# Power_Sources_and_Supply.net
KiCad netlist of a schematic drawn in Altium Designer
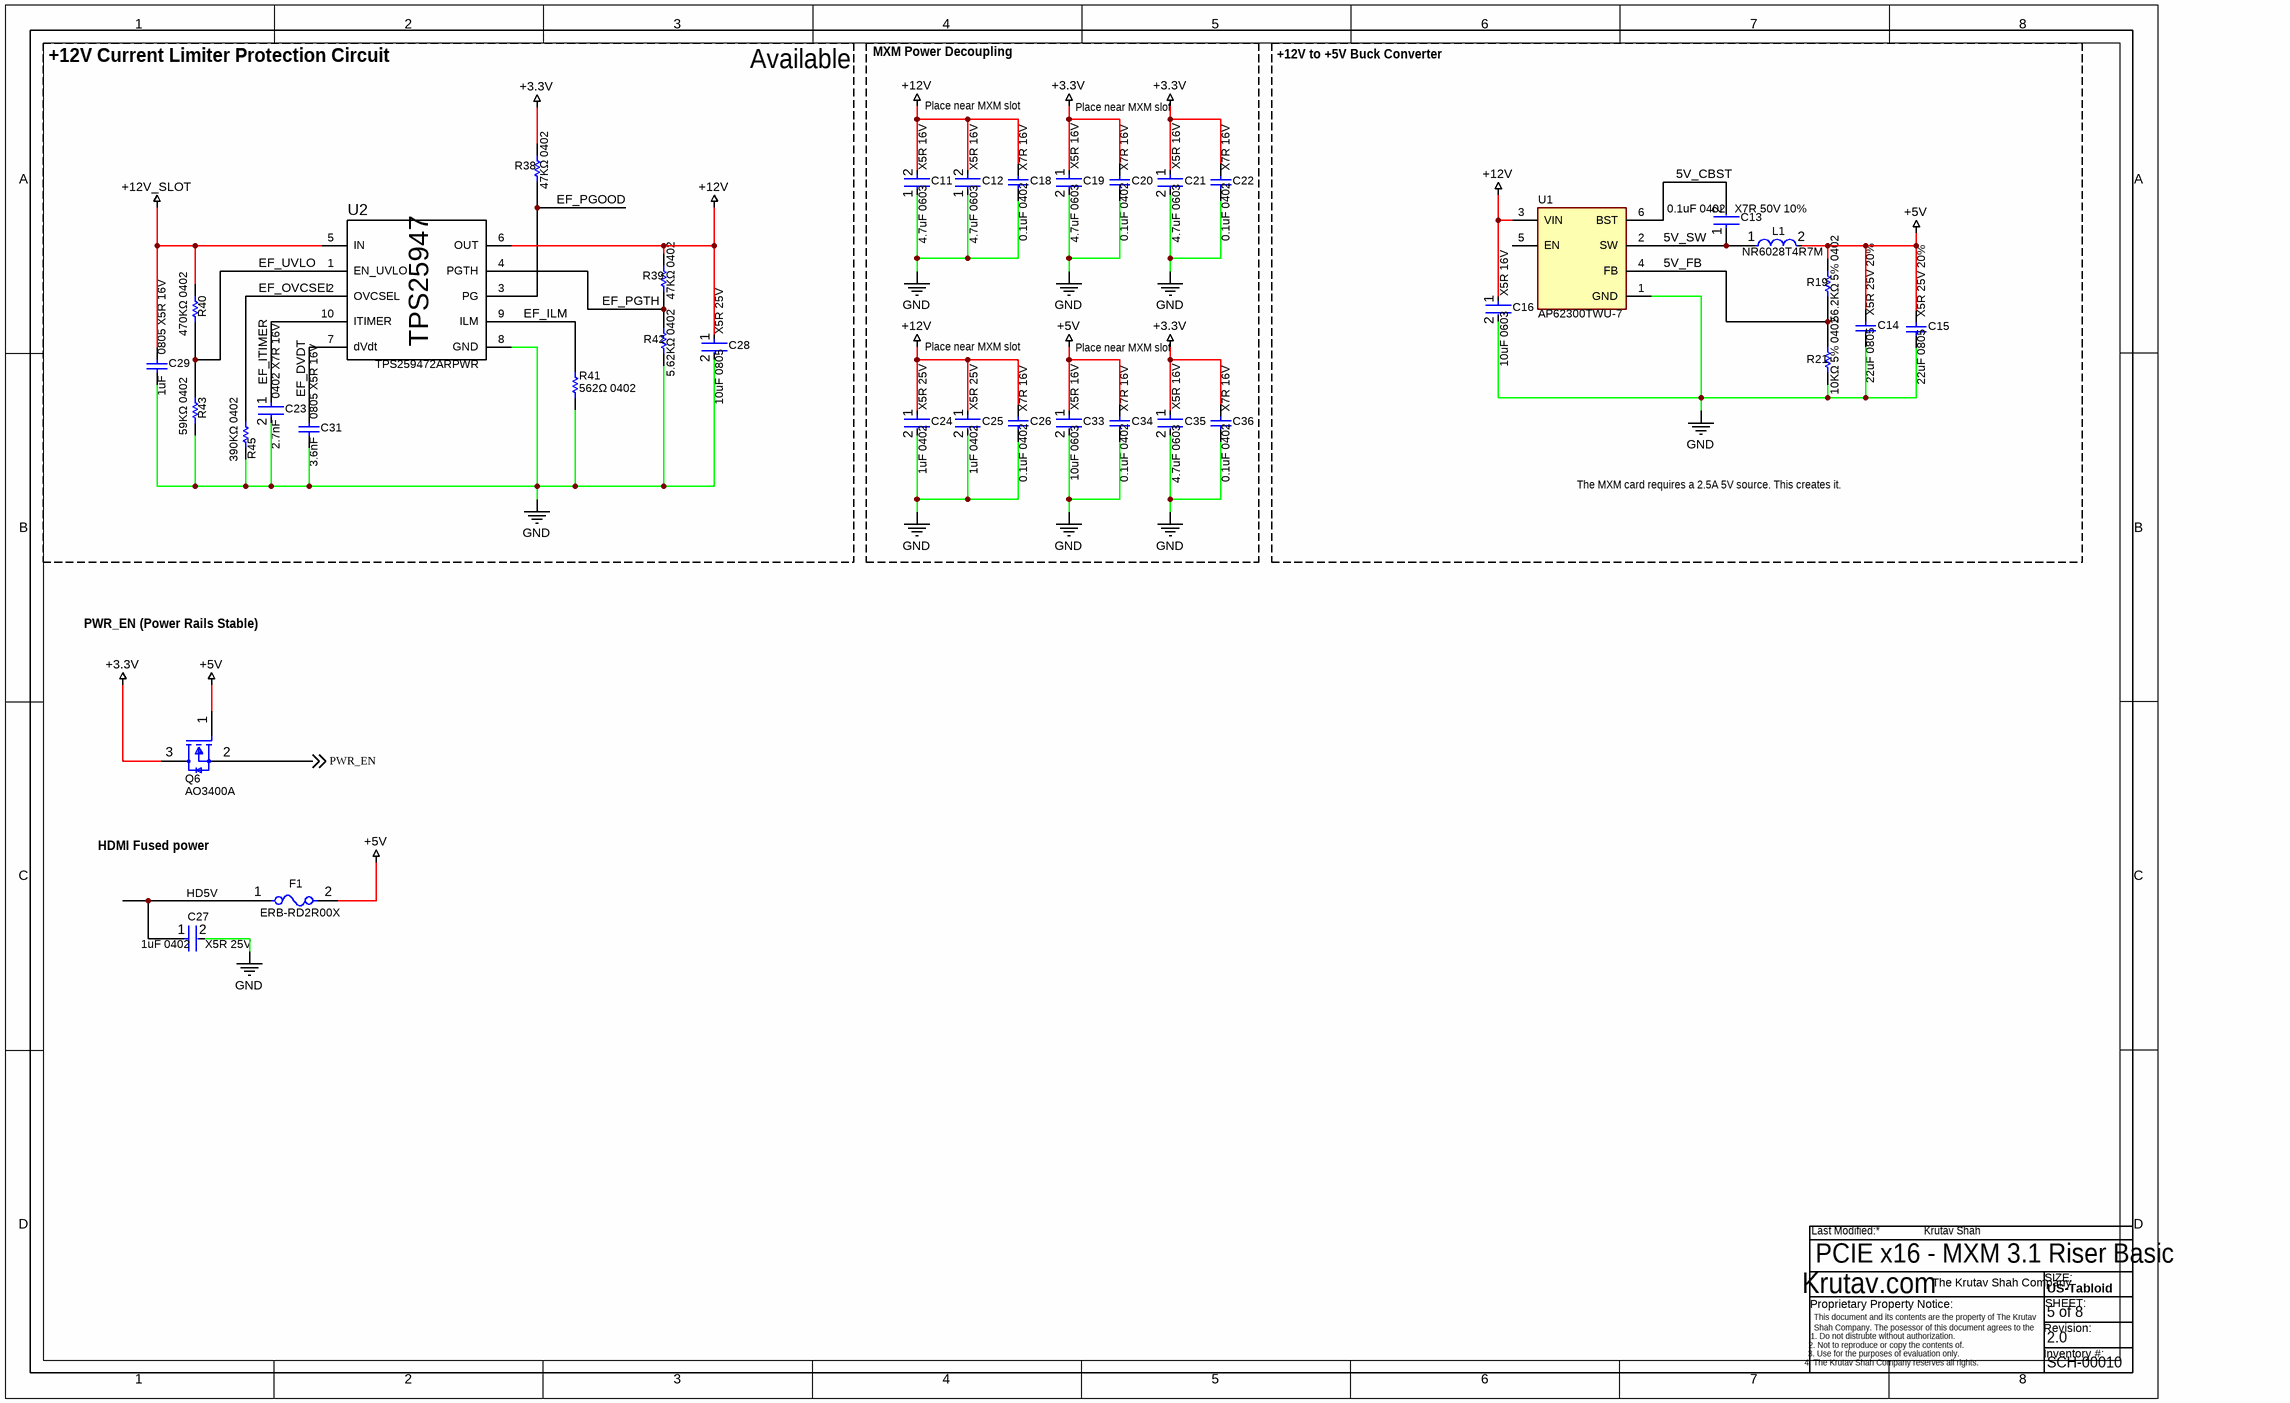
[diagram p0: Power Sources and Supply.SchDoc]

(export (version "E")
  (design (tool "Eeschema 10.0.6"))
  (components
    (comp (ref "C11")
      (value "4.7uF 0603     X5R 16V")
      (footprint "FP-C1608-080-0_1-IPC_C")
      (description "Multilayer Ceramic Capacitors 4.7μF ±10% 16V X5R SMD 0603")
      (fields (field (name "TOLERANCE") "10%") (field (name "VOLTAGE") "16V"))
      (libsource (lib "Altium Content Vault") (part "236180d848d6139a670b325ea6854c9"))
    )
    (comp (ref "C12")
      (value "4.7uF 0603     X5R 16V")
      (footprint "FP-C1608-080-0_1-IPC_C")
      (description "Multilayer Ceramic Capacitors 4.7μF ±10% 16V X5R SMD 0603")
      (fields (field (name "TOLERANCE") "10%") (field (name "VOLTAGE") "16V"))
      (libsource (lib "Altium Content Vault") (part "236180d848d6139a670b325ea6854c9"))
    )
    (comp (ref "C13")
      (value "0.1uF 0402   X7R 50V 10%")
      (footprint "FP-CL779-IPC_C")
      (description "Cap Ceramic 100nF 50V X7R ±10% SMD 0402 +125°C Paper T/R")
      (libsource (lib "Altium Content Vault") (part "b4654b650e69147ec39a6b967a45e02"))
    )
    (comp (ref "C14")
      (value "22uF 0805    X5R 25V 20%")
      (footprint "CAPC2013X140X45LL15T25")
      (description "Multi-layer Ceramic Capacitor, 22 uF, -55 to 85 degC, 2-Pin SMD (0805), RoHS, Tape and Reel")
      (fields (field (name "MANUFACTURER") "Samsung Electro-Mechanics") (field (name "TOLERANCE") "±20%"))
      (libsource (lib "Altium Content Vault") (part "CAP-NP-2"))
    )
    (comp (ref "C15")
      (value "22uF 0805    X5R 25V 20%")
      (footprint "CAPC2013X140X45LL15T25")
      (description "Multi-layer Ceramic Capacitor, 22 uF, -55 to 85 degC, 2-Pin SMD (0805), RoHS, Tape and Reel")
      (fields (field (name "MANUFACTURER") "Samsung Electro-Mechanics") (field (name "TOLERANCE") "±20%"))
      (libsource (lib "Altium Content Vault") (part "CAP-NP-2"))
    )
    (comp (ref "C16")
      (value "10uF 0603     X5R 16V")
      (footprint "FP-CL21-IPC_A")
      (description "CL10A106KP8NNNC Series 0603 10uF 10V ±10% Tolerance X5R Multilayer Ceramic Chip Capacitor")
      (fields (field (name "TOLERANCE") "10%"))
      (libsource (lib "Altium Content Vault") (part "b4654b650e69147ec39a6b967a45e02"))
    )
    (comp (ref "C18")
      (value "0.1uF 0402    X7R 16V")
      (footprint "CAPC1050X55X23ML05T13")
      (description "Chip Capacitor, 100 nF, +/- 10%, 16 V, -55 to 125 degC, 0402 (1005 Metric), RoHS, Tape and Reel")
      (fields (field (name "MANUFACTURER") "Samsung Electro-Mechanics"))
      (libsource (lib "Altium Content Vault") (part "CAP-NP-2"))
    )
    (comp (ref "C19")
      (value "4.7uF 0603     X5R 16V")
      (footprint "FP-CL21-IPC_A")
      (description "CL21 Series 0805 4.7uF 25V ±10% Tolerance X5R Multilayer Ceramic Chip Capacitor")
      (fields (field (name "TOLERANCE") "10%"))
      (libsource (lib "Altium Content Vault") (part "b4654b650e69147ec39a6b967a45e02"))
    )
    (comp (ref "C20")
      (value "0.1uF 0402    X7R 16V")
      (footprint "CAPC1050X55X23ML05T13")
      (description "Chip Capacitor, 100 nF, +/- 10%, 16 V, -55 to 125 degC, 0402 (1005 Metric), RoHS, Tape and Reel")
      (fields (field (name "MANUFACTURER") "Samsung Electro-Mechanics"))
      (libsource (lib "Altium Content Vault") (part "CAP-NP-2"))
    )
    (comp (ref "C21")
      (value "4.7uF 0603     X5R 16V")
      (footprint "FP-CL21-IPC_A")
      (description "CL21 Series 0805 4.7uF 25V ±10% Tolerance X5R Multilayer Ceramic Chip Capacitor")
      (fields (field (name "TOLERANCE") "10%"))
      (libsource (lib "Altium Content Vault") (part "b4654b650e69147ec39a6b967a45e02"))
    )
    (comp (ref "C22")
      (value "0.1uF 0402    X7R 16V")
      (footprint "CAPC1050X55X23ML05T13")
      (description "Chip Capacitor, 100 nF, +/- 10%, 16 V, -55 to 125 degC, 0402 (1005 Metric), RoHS, Tape and Reel")
      (fields (field (name "MANUFACTURER") "Samsung Electro-Mechanics"))
      (libsource (lib "Altium Content Vault") (part "CAP-NP-2"))
    )
    (comp (ref "C23")
      (value "2.7nF       0402 X7R 16V")
      (footprint "FP-C0402-BB-MFG")
      (description "CAP CER 2700PF 16V X7R 0402")
      (fields
        (field (name "OCTOPART") "https://octopart.com/c0402c272k4ractu-kemet-12595530")
        (field (name "MANUFACTURER PART NUMBER") "C0402C272K4RACTU")
      )
      (libsource (lib "Altium Content Vault") (part "b4654b650e69147ec39a6b967a45e02"))
    )
    (comp (ref "C24")
      (value "1uF 0402     X5R 25V")
      (footprint "FP-CL542-IPC_C")
      (description "Cap Ceramic 1uF 25V X5R ±10% SMD 0402 +85°C Paper T/R")
      (fields (field (name "TOLERANCE") "10%"))
      (libsource (lib "Altium Content Vault") (part "b4654b650e69147ec39a6b967a45e02"))
    )
    (comp (ref "C25")
      (value "1uF 0402     X5R 25V")
      (footprint "FP-CL542-IPC_C")
      (description "Cap Ceramic 1uF 25V X5R ±10% SMD 0402 +85°C Paper T/R")
      (fields (field (name "TOLERANCE") "10%"))
      (libsource (lib "Altium Content Vault") (part "b4654b650e69147ec39a6b967a45e02"))
    )
    (comp (ref "C26")
      (value "0.1uF 0402    X7R 16V")
      (footprint "CAPC1050X55X23ML05T13")
      (description "Chip Capacitor, 100 nF, +/- 10%, 16 V, -55 to 125 degC, 0402 (1005 Metric), RoHS, Tape and Reel")
      (fields (field (name "MANUFACTURER") "Samsung Electro-Mechanics"))
      (libsource (lib "Altium Content Vault") (part "CAP-NP-2"))
    )
    (comp (ref "C27")
      (value "1uF 0402     X5R 25V")
      (footprint "FP-CL542-IPC_C")
      (description "Cap Ceramic 1uF 25V X5R ±10% SMD 0402 +85°C Paper T/R")
      (fields (field (name "TOLERANCE") "10%"))
      (libsource (lib "Altium Content Vault") (part "b4654b650e69147ec39a6b967a45e02"))
    )
    (comp (ref "C28")
      (value "10uF 0805     X5R 25V")
      (footprint "FP-CL21-IPC_A")
      (description "CL21 Series 0805 10uF 25V ±10% Tolerance X5R Multilayer Ceramic Chip Capacitor")
      (fields (field (name "TOLERANCE") "10%"))
      (libsource (lib "Altium Content Vault") (part "b4654b650e69147ec39a6b967a45e02"))
    )
    (comp (ref "C29")
      (value "1uF       0805 X5R 16V")
      (footprint "CAPC0603X33X15NL03T05")
      (fields (field (name "MANUFACTURER") "Samsung") (field (name "PART NUMBER") "CL03A224MQ3NNNC"))
      (libsource (lib "Altium Content Vault") (part "CAP"))
    )
    (comp (ref "C31")
      (value "3.6nF      0805 X5R 16V")
      (footprint "CAPC0603X33X15NL03T05")
      (fields (field (name "MANUFACTURER") "Samsung") (field (name "PART NUMBER") "CL03A224MQ3NNNC"))
      (libsource (lib "Altium Content Vault") (part "CAP"))
    )
    (comp (ref "C33")
      (value "10uF 0603     X5R 16V")
      (footprint "FP-CL21-IPC_A")
      (description "CL10A106KP8NNNC Series 0603 10uF 10V ±10% Tolerance X5R Multilayer Ceramic Chip Capacitor")
      (fields (field (name "TOLERANCE") "10%"))
      (libsource (lib "Altium Content Vault") (part "b4654b650e69147ec39a6b967a45e02"))
    )
    (comp (ref "C34")
      (value "0.1uF 0402    X7R 16V")
      (footprint "CAPC1050X55X23ML05T13")
      (description "Chip Capacitor, 100 nF, +/- 10%, 16 V, -55 to 125 degC, 0402 (1005 Metric), RoHS, Tape and Reel")
      (fields (field (name "MANUFACTURER") "Samsung Electro-Mechanics"))
      (libsource (lib "Altium Content Vault") (part "CAP-NP-2"))
    )
    (comp (ref "C35")
      (value "4.7uF 0603     X5R 16V")
      (footprint "FP-CL21-IPC_A")
      (description "CL21 Series 0805 4.7uF 25V ±10% Tolerance X5R Multilayer Ceramic Chip Capacitor")
      (fields (field (name "TOLERANCE") "10%"))
      (libsource (lib "Altium Content Vault") (part "b4654b650e69147ec39a6b967a45e02"))
    )
    (comp (ref "C36")
      (value "0.1uF 0402    X7R 16V")
      (footprint "CAPC1050X55X23ML05T13")
      (description "Chip Capacitor, 100 nF, +/- 10%, 16 V, -55 to 125 degC, 0402 (1005 Metric), RoHS, Tape and Reel")
      (fields (field (name "MANUFACTURER") "Samsung Electro-Mechanics"))
      (libsource (lib "Altium Content Vault") (part "CAP-NP-2"))
    )
    (comp (ref "F1")
      (value "ERB-RD2R00X")
      (footprint "FP-ERBRD-MFG")
      (description "FUSE BOARD MOUNT 2A 32VDC 0402")
      (fields
        (field (name "OCTOPART") "https://octopart.com/erb-rd2r00x-panasonic-21220532")
        (field (name "MANUFACTURER") "Panasonic Electronic Components")
      )
      (libsource (lib "Altium Content Vault") (part "5bcf9b9f640e542cf0359d10258e979"))
    )
    (comp (ref "L1")
      (value "NR6028T4R7M")
      (footprint "FP-NR6028-MFG")
      (description "SMD Power Inductors 4.7uH ±20% 2.7A 40.3mΩ")
      (fields (field (name "TOLERANCE") "20%"))
      (libsource (lib "Altium Content Vault") (part "725321dda6339637d4d059423bc1c3c"))
    )
    (comp (ref "Q6")
      (value "AO3400A")
      (footprint "FP-SOT23-MFG")
      (description "MOSFET N-CH 30V 5.7A SOT23")
      (libsource (lib "Altium Content Vault") (part "0a9ea7c96deaaede766a5b531c28de0"))
    )
    (comp (ref "R19")
      (value "56.2KΩ 5% 0402")
      (footprint "RESC0201(0603)_L")
      (description "1M 0.05W 1% 0201 (0603 Metric)  SMD")
      (fields (field (name "TOLERANCE") "1 %") (field (name "POWER") "0.05 W"))
      (libsource (lib "Altium Content Vault") (part "RES"))
    )
    (comp (ref "R21")
      (value "10KΩ 5% 0402")
      (footprint "RESC0201(0603)_L")
      (description "1M 0.05W 1% 0201 (0603 Metric)  SMD")
      (fields (field (name "TOLERANCE") "1 %") (field (name "POWER") "0.05 W"))
      (libsource (lib "Altium Content Vault") (part "RES"))
    )
    (comp (ref "R38")
      (value "47KΩ 0402")
      (footprint "RESC0201(0603)_L")
      (description "1M 0.05W 1% 0201 (0603 Metric)  SMD")
      (fields (field (name "TOLERANCE") "1 %") (field (name "POWER") "0.05 W"))
      (libsource (lib "Altium Content Vault") (part "RES"))
    )
    (comp (ref "R39")
      (value "47KΩ 0402")
      (footprint "RESC0201(0603)_L")
      (description "1M 0.05W 1% 0201 (0603 Metric)  SMD")
      (fields (field (name "TOLERANCE") "1 %") (field (name "POWER") "0.05 W"))
      (libsource (lib "Altium Content Vault") (part "RES"))
    )
    (comp (ref "R40")
      (value "470KΩ 0402")
      (footprint "RESC0201(0603)_L")
      (description "0402WGF4703TCE")
      (fields (field (name "TOLERANCE") "1 %") (field (name "POWER") "0.05 W"))
      (libsource (lib "Altium Content Vault") (part "RES"))
    )
    (comp (ref "R41")
      (value "562Ω 0402")
      (footprint "RESC0201(0603)_L")
      (description "1M 0.05W 1% 0201 (0603 Metric)  SMD")
      (fields (field (name "TOLERANCE") "1 %") (field (name "POWER") "0.05 W"))
      (libsource (lib "Altium Content Vault") (part "RES"))
    )
    (comp (ref "R42")
      (value "5.62KΩ 0402")
      (footprint "RESC0201(0603)_L")
      (description "1M 0.05W 1% 0201 (0603 Metric)  SMD")
      (fields (field (name "TOLERANCE") "1 %") (field (name "POWER") "0.05 W"))
      (libsource (lib "Altium Content Vault") (part "RES"))
    )
    (comp (ref "R43")
      (value "59KΩ 0402")
      (footprint "RESC0201(0603)_L")
      (description "1M 0.05W 1% 0201 (0603 Metric)  SMD")
      (fields (field (name "TOLERANCE") "1 %") (field (name "POWER") "0.05 W"))
      (libsource (lib "Altium Content Vault") (part "RES"))
    )
    (comp (ref "R45")
      (value "390KΩ 0402")
      (footprint "RESC0201(0603)_L")
      (description "1M 0.05W 1% 0201 (0603 Metric)  SMD")
      (fields (field (name "TOLERANCE") "1 %") (field (name "POWER") "0.05 W"))
      (libsource (lib "Altium Content Vault") (part "RES"))
    )
    (comp (ref "U1")
      (value "AP62300TWU-7")
      (footprint "FP-TSOT26-MFG")
      (description "IC REG BUCK ADJUSTABLE 2A TSOT26")
      (fields
        (field (name "OCTOPART") "https://octopart.com/ap63200wu-7-diodes+inc.-98099548")
        (field (name "MANUFACTURER") "Diodes Inc.")
      )
      (libsource (lib "Altium Content Vault") (part "2ae3aed49e7ee94ca813948749813a1"))
    )
    (comp (ref "U2")
      (value "TPS259472ARPWR")
      (footprint "RPW0010A-MFG")
      (description "No Description Available")
      (fields
        (field (name "MANUFACTURER_PART_NUMBER") "TPS259474ARPWR")
        (field (name "COPYRIGHT") "Copyright (C) 2021 Ultra Librarian. All rights reserved.")
      )
      (libsource (lib "TPS259474ARPWR") (part "TPS259474ARPWR"))
    )
  )
  (nets
    (net (code "1") (name "+3.3V") (class "Default")
      (node (ref "C19") (pin "1") (pinfunction "1_1") (pintype "passive"))
      (node (ref "C20") (pin "2") (pinfunction "2_2") (pintype "passive"))
      (node (ref "C21") (pin "1") (pinfunction "1_1") (pintype "passive"))
      (node (ref "C22") (pin "2") (pinfunction "2_2") (pintype "passive"))
      (node (ref "C35") (pin "1") (pinfunction "1_1") (pintype "passive"))
      (node (ref "C36") (pin "2") (pinfunction "2_2") (pintype "passive"))
      (node (ref "Q6") (pin "3") (pinfunction "D_3") (pintype "passive"))
      (node (ref "R38") (pin "1") (pinfunction "1_1") (pintype "passive"))
    )
    (net (code "2") (name "+5V") (class "Default")
      (node (ref "C14") (pin "2") (pinfunction "2_2") (pintype "passive"))
      (node (ref "C15") (pin "2") (pinfunction "2_2") (pintype "passive"))
      (node (ref "C33") (pin "1") (pinfunction "1_1") (pintype "passive"))
      (node (ref "C34") (pin "2") (pinfunction "2_2") (pintype "passive"))
      (node (ref "F1") (pin "2") (pinfunction "2_2") (pintype "passive"))
      (node (ref "L1") (pin "2") (pinfunction "2_2") (pintype "passive"))
      (node (ref "Q6") (pin "1") (pinfunction "G_1") (pintype "passive"))
      (node (ref "R19") (pin "1") (pinfunction "1_1") (pintype "passive"))
    )
    (net (code "3") (name "+12V") (class "Default")
      (node (ref "C11") (pin "2") (pinfunction "2_2") (pintype "passive"))
      (node (ref "C12") (pin "2") (pinfunction "2_2") (pintype "passive"))
      (node (ref "C16") (pin "1") (pinfunction "1_1") (pintype "passive"))
      (node (ref "C18") (pin "2") (pinfunction "2_2") (pintype "passive"))
      (node (ref "C24") (pin "1") (pinfunction "1_1") (pintype "passive"))
      (node (ref "C25") (pin "1") (pinfunction "1_1") (pintype "passive"))
      (node (ref "C26") (pin "2") (pinfunction "2_2") (pintype "passive"))
      (node (ref "C28") (pin "1") (pinfunction "1_1") (pintype "passive"))
      (node (ref "R39") (pin "1") (pinfunction "1_1") (pintype "passive"))
      (node (ref "U1") (pin "3") (pinfunction "VIN_3") (pintype "passive"))
      (node (ref "U2") (pin "6") (pinfunction "OUT_6") (pintype "passive"))
    )
    (net (code "4") (name "+12V_SLOT") (class "Default")
      (node (ref "C29") (pin "1") (pinfunction "1_1") (pintype "passive"))
      (node (ref "R40") (pin "1") (pinfunction "1_1") (pintype "passive"))
      (node (ref "U2") (pin "5") (pinfunction "IN_5") (pintype "passive"))
    )
    (net (code "5") (name "/5V_CBST") (class "Default")
      (node (ref "C13") (pin "2") (pinfunction "2_2") (pintype "passive"))
      (node (ref "U1") (pin "6") (pinfunction "BST_6") (pintype "passive"))
    )
    (net (code "6") (name "/5V_FB") (class "Default")
      (node (ref "R19") (pin "2") (pinfunction "2_2") (pintype "passive"))
      (node (ref "R21") (pin "2") (pinfunction "2_2") (pintype "passive"))
      (node (ref "U1") (pin "4") (pinfunction "FB_4") (pintype "passive"))
    )
    (net (code "7") (name "/5V_SW") (class "Default")
      (node (ref "C13") (pin "1") (pinfunction "1_1") (pintype "passive"))
      (node (ref "L1") (pin "1") (pinfunction "1_1") (pintype "passive"))
      (node (ref "U1") (pin "2") (pinfunction "SW_2") (pintype "passive"))
    )
    (net (code "8") (name "/EF_DVDT") (class "Default")
      (node (ref "C31") (pin "1") (pinfunction "1_1") (pintype "passive"))
      (node (ref "U2") (pin "7") (pinfunction "dVdt_7") (pintype "passive"))
    )
    (net (code "9") (name "/EF_ILM") (class "Default")
      (node (ref "R41") (pin "1") (pinfunction "1_1") (pintype "passive"))
      (node (ref "U2") (pin "9") (pinfunction "ILM_9") (pintype "passive"))
    )
    (net (code "10") (name "/EF_ITIMER") (class "Default")
      (node (ref "C23") (pin "1") (pinfunction "1_1") (pintype "passive"))
      (node (ref "U2") (pin "10") (pinfunction "ITIMER_10") (pintype "passive"))
    )
    (net (code "11") (name "/EF_OVCSEL") (class "Default")
      (node (ref "R45") (pin "1") (pinfunction "1_1") (pintype "passive"))
      (node (ref "U2") (pin "2") (pinfunction "OVCSEL_2") (pintype "passive"))
    )
    (net (code "12") (name "/EF_PGOOD") (class "Default")
      (node (ref "R38") (pin "2") (pinfunction "2_2") (pintype "passive"))
      (node (ref "U2") (pin "3") (pinfunction "PG_3") (pintype "passive"))
    )
    (net (code "13") (name "/EF_PGTH") (class "Default")
      (node (ref "R39") (pin "2") (pinfunction "2_2") (pintype "passive"))
      (node (ref "R42") (pin "2") (pinfunction "2_2") (pintype "passive"))
      (node (ref "U2") (pin "4") (pinfunction "PGTH_4") (pintype "passive"))
    )
    (net (code "14") (name "/EF_UVLO") (class "Default")
      (node (ref "R40") (pin "2") (pinfunction "2_2") (pintype "passive"))
      (node (ref "R43") (pin "2") (pinfunction "2_2") (pintype "passive"))
      (node (ref "U2") (pin "1") (pinfunction "EN_UVLO_1") (pintype "passive"))
    )
    (net (code "15") (name "GND") (class "Default")
      (node (ref "C11") (pin "1") (pinfunction "1_1") (pintype "passive"))
      (node (ref "C12") (pin "1") (pinfunction "1_1") (pintype "passive"))
      (node (ref "C14") (pin "1") (pinfunction "1_1") (pintype "passive"))
      (node (ref "C15") (pin "1") (pinfunction "1_1") (pintype "passive"))
      (node (ref "C16") (pin "2") (pinfunction "2_2") (pintype "passive"))
      (node (ref "C18") (pin "1") (pinfunction "1_1") (pintype "passive"))
      (node (ref "C19") (pin "2") (pinfunction "2_2") (pintype "passive"))
      (node (ref "C20") (pin "1") (pinfunction "1_1") (pintype "passive"))
      (node (ref "C21") (pin "2") (pinfunction "2_2") (pintype "passive"))
      (node (ref "C22") (pin "1") (pinfunction "1_1") (pintype "passive"))
      (node (ref "C23") (pin "2") (pinfunction "2_2") (pintype "passive"))
      (node (ref "C24") (pin "2") (pinfunction "2_2") (pintype "passive"))
      (node (ref "C25") (pin "2") (pinfunction "2_2") (pintype "passive"))
      (node (ref "C26") (pin "1") (pinfunction "1_1") (pintype "passive"))
      (node (ref "C27") (pin "2") (pinfunction "2_2") (pintype "passive"))
      (node (ref "C28") (pin "2") (pinfunction "2_2") (pintype "passive"))
      (node (ref "C29") (pin "2") (pinfunction "2_2") (pintype "passive"))
      (node (ref "C31") (pin "2") (pinfunction "2_2") (pintype "passive"))
      (node (ref "C33") (pin "2") (pinfunction "2_2") (pintype "passive"))
      (node (ref "C34") (pin "1") (pinfunction "1_1") (pintype "passive"))
      (node (ref "C35") (pin "2") (pinfunction "2_2") (pintype "passive"))
      (node (ref "C36") (pin "1") (pinfunction "1_1") (pintype "passive"))
      (node (ref "R21") (pin "1") (pinfunction "1_1") (pintype "passive"))
      (node (ref "R41") (pin "2") (pinfunction "2_2") (pintype "passive"))
      (node (ref "R42") (pin "1") (pinfunction "1_1") (pintype "passive"))
      (node (ref "R43") (pin "1") (pinfunction "1_1") (pintype "passive"))
      (node (ref "R45") (pin "2") (pinfunction "2_2") (pintype "passive"))
      (node (ref "U1") (pin "1") (pinfunction "GND_1") (pintype "passive"))
      (node (ref "U2") (pin "8") (pinfunction "GND_8") (pintype "passive"))
    )
    (net (code "16") (name "Net-(C27-Pad1)") (class "Default")
      (node (ref "C27") (pin "1") (pinfunction "1_1") (pintype "passive"))
      (node (ref "F1") (pin "1") (pinfunction "1_1") (pintype "passive"))
    )
    (net (code "17") (name "PWR_EN") (class "Default")
      (node (ref "Q6") (pin "2") (pinfunction "S_2") (pintype "passive"))
    )
    (net (code "18") (name "unconnected-(U1-EN-Pad5)") (class "Default")
      (node (ref "U1") (pin "5") (pinfunction "EN_5") (pintype "passive"))
    )
  )
)
